# Supply_12V.net
KiCad netlist of a schematic drawn in Altium Designer
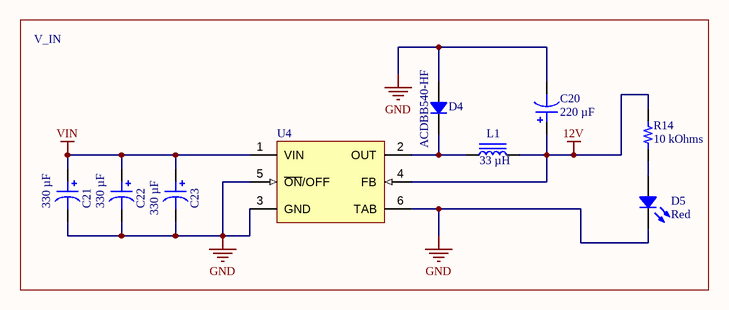
[diagram p0: Supply_12V.SchDoc]

(export (version "E")
  (design (tool "Eeschema 10.0.6"))
  (components
    (comp (ref "C20")
      (value "220 µF")
      (footprint "CAP ALSMD 8.3MM H10.5MM")
      (description "CAP ALUM 220UF 20% 25V SMD")
      (fields (field (name "MANUFACTURER") "Rubycon") (field (name "PART NUMBER") "25SKV220M8X10.5"))
      (libsource (lib "Celestial Altium Library - altium_library") (part "Polarised Capacitor"))
    )
    (comp (ref "C21")
      (value "330 µF")
      (footprint "CAP ALSMD 8.3MM H10.5MM")
      (description "CAP ALUM 330UF 20% 35V SMD")
      (fields
        (field (name "PART NUMBER") "EMZS350ARA331MHA0G")
        (field (name "MANUFACTURER") "United Chemi-Con")
      )
      (libsource (lib "Celestial Altium Library - altium_library") (part "Polarised Capacitor"))
    )
    (comp (ref "C22")
      (value "330 µF")
      (footprint "CAP ALSMD 8.3MM H10.5MM")
      (description "CAP ALUM 330UF 20% 35V SMD")
      (fields
        (field (name "PART NUMBER") "EMZS350ARA331MHA0G")
        (field (name "MANUFACTURER") "United Chemi-Con")
      )
      (libsource (lib "Celestial Altium Library - altium_library") (part "Polarised Capacitor"))
    )
    (comp (ref "C23")
      (value "330 µF")
      (footprint "CAP ALSMD 8.3MM H10.5MM")
      (description "CAP ALUM 330UF 20% 35V SMD")
      (fields
        (field (name "PART NUMBER") "EMZS350ARA331MHA0G")
        (field (name "MANUFACTURER") "United Chemi-Con")
      )
      (libsource (lib "Celestial Altium Library - altium_library") (part "Polarised Capacitor"))
    )
    (comp (ref "D4")
      (value "ACDBB540-HF")
      (footprint "DO214AA SMB")
      (description "DIODE SCHOTTKY 40V 5A DO214AA")
      (fields (field (name "MANUFACTURER") "Comchip Technology"))
      (libsource (lib "Celestial Altium Library - altium_library") (part "Diode"))
    )
    (comp (ref "D5")
      (value "Red")
      (footprint "LED 0603_1608 RED")
      (description "LED RED CLEAR 0603 SMD")
      (fields
        (field (name "PART NUMBER") "LR Q976.01-P2R2-1")
        (field (name "MANUFACTURER") "ams-OSRAM USA Inc.")
      )
      (libsource (lib "Celestial Altium Library - altium_library") (part "LED"))
    )
    (comp (ref "L1")
      (value "33 µH")
      (footprint "BOURNS SRR1280")
      (description "FIXED IND 33UH 3.5A 57 MOHM SMD")
      (fields (field (name "TOLERANCE") "±20%") (field (name "PART NUMBER") "SRR1280-330M"))
      (libsource (lib "Celestial Altium Library - altium_library") (part "Inductor"))
    )
    (comp (ref "R14")
      (value "10 kOhms")
      (footprint "YAGEO RES 0603_1608")
      (description "RES SMD 10K OHM 5% 1/10W 0603")
      (fields (field (name "PART NUMBER") "AC0603JR-0710KL") (field (name "MANUFACTURER") "Yageo"))
      (libsource (lib "Celestial Altium Library - altium_library") (part "Resistor"))
    )
    (comp (ref "U4")
      (value "~")
      (footprint "KTT0005B_M")
      (description "SIMPLE SWITCHER® 3A Step-Down Voltage Regulator, 5-pin TO-263, Pb-Free")
      (fields (field (name "MANUFACTURER") "Texas Instruments"))
      (libsource (lib "CPAP_POWER") (part "LM2576S-12/NOPB"))
    )
  )
  (nets
    (net (code "1") (name "12V") (class "Default")
      (node (ref "C20") (pin "1") (pinfunction "1_1") (pintype "passive"))
      (node (ref "L1") (pin "2") (pinfunction "2_2") (pintype "passive"))
      (node (ref "R14") (pin "2") (pinfunction "2_2") (pintype "passive"))
      (node (ref "U4") (pin "4") (pinfunction "FB_4") (pintype "input"))
    )
    (net (code "2") (name "GND") (class "Default")
      (node (ref "C20") (pin "2") (pinfunction "2_2") (pintype "passive"))
      (node (ref "C21") (pin "2") (pinfunction "2_2") (pintype "passive"))
      (node (ref "C22") (pin "2") (pinfunction "2_2") (pintype "passive"))
      (node (ref "C23") (pin "2") (pinfunction "2_2") (pintype "passive"))
      (node (ref "D4") (pin "1") (pinfunction "1_1") (pintype "passive"))
      (node (ref "D5") (pin "2") (pinfunction "2_2") (pintype "passive"))
      (node (ref "U4") (pin "3") (pinfunction "GND_3") (pintype "power_in"))
      (node (ref "U4") (pin "5") (pinfunction "~{ON}/OFF_5") (pintype "input"))
      (node (ref "U4") (pin "6") (pinfunction "TAB_6") (pintype "power_in"))
    )
    (net (code "3") (name "Net-(D5-Pad1)") (class "Default")
      (node (ref "D5") (pin "1") (pinfunction "1_1") (pintype "passive"))
      (node (ref "R14") (pin "1") (pinfunction "1_1") (pintype "passive"))
    )
    (net (code "4") (name "Net-(U4-OUT)") (class "Default")
      (node (ref "D4") (pin "2") (pinfunction "2_2") (pintype "passive"))
      (node (ref "L1") (pin "1") (pinfunction "1_1") (pintype "passive"))
      (node (ref "U4") (pin "2") (pinfunction "OUT_2") (pintype "power_in"))
    )
    (net (code "5") (name "VIN") (class "Default")
      (node (ref "C21") (pin "1") (pinfunction "1_1") (pintype "passive"))
      (node (ref "C22") (pin "1") (pinfunction "1_1") (pintype "passive"))
      (node (ref "C23") (pin "1") (pinfunction "1_1") (pintype "passive"))
      (node (ref "U4") (pin "1") (pinfunction "VIN_1") (pintype "power_in"))
    )
  )
)
